# Board.net
KiCad netlist of a schematic drawn in EasyEDA Pro
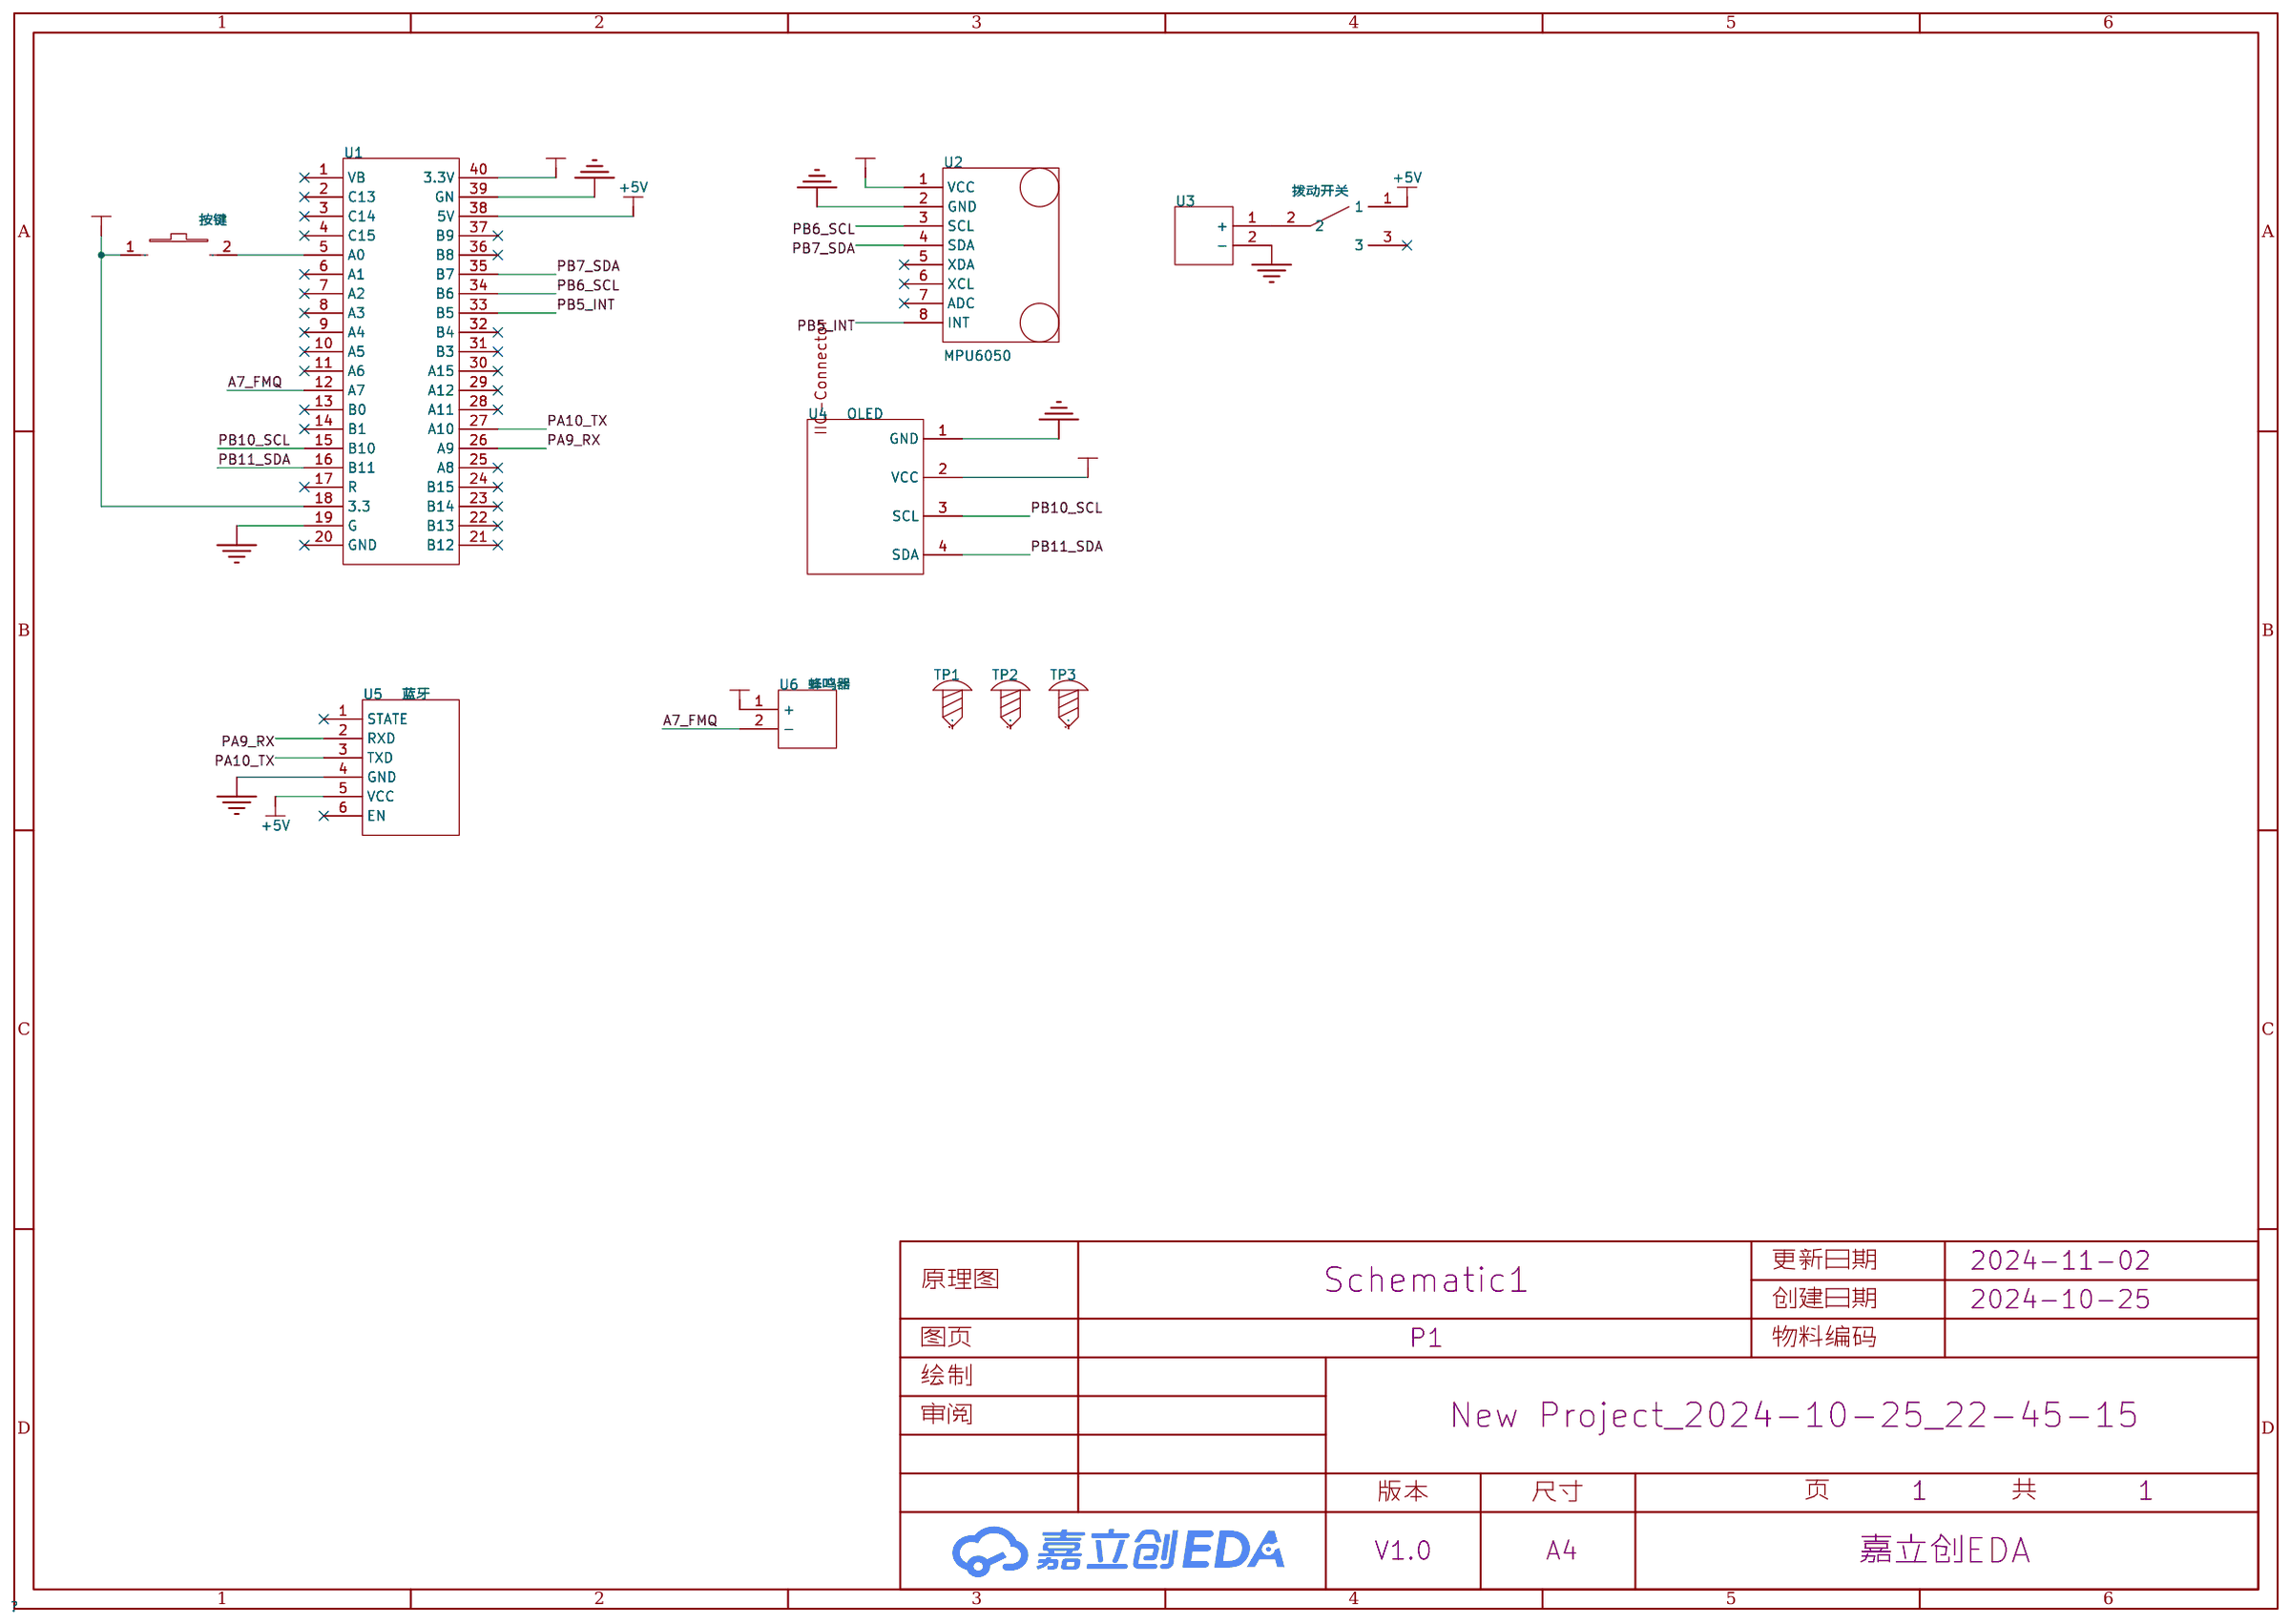
[diagram p0: schematic sheet]

(export (version "E")
  (design (tool "Eeschema 10.0.6"))
  (components
    (comp (ref "J1")
      (value "按键")
      (footprint "easyedapro:SW-SMD_L6.0-W3.6-LS8.0")
      (fields (field (name "Manufacturer Part") "轻触按键 3x6x2.5mm"))
      (libsource (lib "easyedapro") (part "按键"))
    )
    (comp (ref "J2")
      (value "拨动开关")
      (footprint "easyedapro:SS12D00G4 1*3")
      (libsource (lib "easyedapro") (part "拨动开关"))
    )
    (comp (ref "TP1") (value "~") (footprint "easyedapro:M3螺丝") (libsource (lib "easyedapro") (part "螺丝孔")))
    (comp (ref "TP2") (value "~") (footprint "easyedapro:M3螺丝") (libsource (lib "easyedapro") (part "螺丝孔")))
    (comp (ref "TP3") (value "~") (footprint "easyedapro:M3螺丝") (libsource (lib "easyedapro") (part "螺丝孔")))
    (comp (ref "U1")
      (value "STM32")
      (footprint "easyedapro:STM32F103C8T6最小系统板")
      (description "STM32F103C最小系统板")
      (libsource (lib "easyedapro") (part "STM32"))
    )
    (comp (ref "U2")
      (value "MPU6050")
      (footprint "easyedapro:MPU6050")
      (libsource (lib "easyedapro") (part "mpu6050"))
    )
    (comp (ref "U3") (value "~") (footprint "easyedapro:锂电池充电") (libsource (lib "easyedapro") (part "锂电池")))
    (comp (ref "U4")
      (value "OLED")
      (footprint "easyedapro:0.96OLED_4P")
      (fields (field (name "Manufacturer Part") "0.96OLED_4P_MODULE_JX"))
      (libsource (lib "easyedapro") (part "oled"))
    )
    (comp (ref "U5") (value "蓝牙") (footprint "easyedapro:蓝牙") (libsource (lib "easyedapro") (part "蓝牙")))
    (comp (ref "U6") (value "蜂鸣器") (footprint "easyedapro:蜂鸣器") (libsource (lib "easyedapro") (part "蜂鸣器")))
  )
  (nets
    (net (code "1") (name "+5V") (class "Default")
      (node (ref "J2") (pin "1") (pinfunction "1_1") (pintype "input"))
      (node (ref "U1") (pin "38") (pinfunction "5V_38") (pintype "bidirectional"))
      (node (ref "U5") (pin "5") (pinfunction "VCC_5") (pintype "input"))
    )
    (net (code "2") (name "/A7_FMQ") (class "Default")
      (node (ref "U1") (pin "12") (pinfunction "A7_12") (pintype "bidirectional"))
      (node (ref "U6") (pin "2") (pinfunction "-_2") (pintype "input"))
    )
    (net (code "3") (name "/PA9_RX") (class "Default")
      (node (ref "U1") (pin "26") (pinfunction "A9_26") (pintype "bidirectional"))
      (node (ref "U5") (pin "2") (pinfunction "RXD_2") (pintype "input"))
    )
    (net (code "4") (name "/PA10_TX") (class "Default")
      (node (ref "U1") (pin "27") (pinfunction "A10_27") (pintype "bidirectional"))
      (node (ref "U5") (pin "3") (pinfunction "TXD_3") (pintype "input"))
    )
    (net (code "5") (name "/PB5_INT") (class "Default")
      (node (ref "U1") (pin "33") (pinfunction "B5_33") (pintype "bidirectional"))
      (node (ref "U2") (pin "8") (pinfunction "INT_8") (pintype "input"))
    )
    (net (code "6") (name "/PB6_SCL") (class "Default")
      (node (ref "U1") (pin "34") (pinfunction "B6_34") (pintype "bidirectional"))
      (node (ref "U2") (pin "3") (pinfunction "SCL_3") (pintype "input"))
    )
    (net (code "7") (name "/PB7_SDA") (class "Default")
      (node (ref "U1") (pin "35") (pinfunction "B7_35") (pintype "bidirectional"))
      (node (ref "U2") (pin "4") (pinfunction "SDA_4") (pintype "input"))
    )
    (net (code "8") (name "/PB10_SCL") (class "Default")
      (node (ref "U1") (pin "15") (pinfunction "B10_15") (pintype "bidirectional"))
      (node (ref "U4") (pin "3") (pinfunction "SCL_3") (pintype "unspecified"))
    )
    (net (code "9") (name "/PB11_SDA") (class "Default")
      (node (ref "U1") (pin "16") (pinfunction "B11_16") (pintype "bidirectional"))
      (node (ref "U4") (pin "4") (pinfunction "SDA_4") (pintype "unspecified"))
    )
    (net (code "10") (name "3V3") (class "Default")
      (node (ref "J1") (pin "1") (pinfunction "1_1") (pintype "input"))
      (node (ref "U1") (pin "18") (pinfunction "3.3_18") (pintype "bidirectional"))
      (node (ref "U1") (pin "40") (pinfunction "3.3V_40") (pintype "bidirectional"))
      (node (ref "U2") (pin "1") (pinfunction "VCC_1") (pintype "input"))
      (node (ref "U4") (pin "2") (pinfunction "VCC_2") (pintype "unspecified"))
      (node (ref "U6") (pin "1") (pinfunction "+_1") (pintype "input"))
    )
    (net (code "11") (name "GND") (class "Default")
      (node (ref "U1") (pin "19") (pinfunction "G_19") (pintype "bidirectional"))
      (node (ref "U1") (pin "39") (pinfunction "GN_39") (pintype "bidirectional"))
      (node (ref "U2") (pin "2") (pinfunction "GND_2") (pintype "input"))
      (node (ref "U3") (pin "2") (pinfunction "-_2") (pintype "input"))
      (node (ref "U4") (pin "1") (pinfunction "GND_1") (pintype "unspecified"))
      (node (ref "U5") (pin "4") (pinfunction "GND_4") (pintype "input"))
    )
    (net (code "12") (name "Net-(U1-A0)") (class "Default")
      (node (ref "J1") (pin "2") (pinfunction "2_2") (pintype "input"))
      (node (ref "U1") (pin "5") (pinfunction "A0_5") (pintype "bidirectional"))
    )
    (net (code "13") (name "Net-(U3-+)") (class "Default")
      (node (ref "J2") (pin "2") (pinfunction "2_2") (pintype "input"))
      (node (ref "U3") (pin "1") (pinfunction "+_1") (pintype "input"))
    )
    (net (code "14") (name "unconnected-(J2-Pad3)") (class "Default")
      (node (ref "J2") (pin "3") (pinfunction "3_3") (pintype "input+no_connect"))
    )
    (net (code "15") (name "unconnected-(TP1-Pad1)") (class "Default")
      (node (ref "TP1") (pin "1") (pinfunction "1_1") (pintype "input"))
    )
    (net (code "16") (name "unconnected-(TP2-Pad1)") (class "Default")
      (node (ref "TP2") (pin "1") (pinfunction "1_1") (pintype "input"))
    )
    (net (code "17") (name "unconnected-(TP3-Pad1)") (class "Default")
      (node (ref "TP3") (pin "1") (pinfunction "1_1") (pintype "input"))
    )
    (net (code "18") (name "unconnected-(U1-A1-Pad6)") (class "Default")
      (node (ref "U1") (pin "6") (pinfunction "A1_6") (pintype "bidirectional+no_connect"))
    )
    (net (code "19") (name "unconnected-(U1-A2-Pad7)") (class "Default")
      (node (ref "U1") (pin "7") (pinfunction "A2_7") (pintype "bidirectional+no_connect"))
    )
    (net (code "20") (name "unconnected-(U1-A3-Pad8)") (class "Default")
      (node (ref "U1") (pin "8") (pinfunction "A3_8") (pintype "bidirectional+no_connect"))
    )
    (net (code "21") (name "unconnected-(U1-A4-Pad9)") (class "Default")
      (node (ref "U1") (pin "9") (pinfunction "A4_9") (pintype "bidirectional+no_connect"))
    )
    (net (code "22") (name "unconnected-(U1-A5-Pad10)") (class "Default")
      (node (ref "U1") (pin "10") (pinfunction "A5_10") (pintype "bidirectional+no_connect"))
    )
    (net (code "23") (name "unconnected-(U1-A6-Pad11)") (class "Default")
      (node (ref "U1") (pin "11") (pinfunction "A6_11") (pintype "bidirectional+no_connect"))
    )
    (net (code "24") (name "unconnected-(U1-A8-Pad25)") (class "Default")
      (node (ref "U1") (pin "25") (pinfunction "A8_25") (pintype "bidirectional+no_connect"))
    )
    (net (code "25") (name "unconnected-(U1-A11-Pad28)") (class "Default")
      (node (ref "U1") (pin "28") (pinfunction "A11_28") (pintype "bidirectional+no_connect"))
    )
    (net (code "26") (name "unconnected-(U1-A12-Pad29)") (class "Default")
      (node (ref "U1") (pin "29") (pinfunction "A12_29") (pintype "bidirectional+no_connect"))
    )
    (net (code "27") (name "unconnected-(U1-A15-Pad30)") (class "Default")
      (node (ref "U1") (pin "30") (pinfunction "A15_30") (pintype "bidirectional+no_connect"))
    )
    (net (code "28") (name "unconnected-(U1-B0-Pad13)") (class "Default")
      (node (ref "U1") (pin "13") (pinfunction "B0_13") (pintype "bidirectional+no_connect"))
    )
    (net (code "29") (name "unconnected-(U1-B1-Pad14)") (class "Default")
      (node (ref "U1") (pin "14") (pinfunction "B1_14") (pintype "bidirectional+no_connect"))
    )
    (net (code "30") (name "unconnected-(U1-B3-Pad31)") (class "Default")
      (node (ref "U1") (pin "31") (pinfunction "B3_31") (pintype "bidirectional+no_connect"))
    )
    (net (code "31") (name "unconnected-(U1-B4-Pad32)") (class "Default")
      (node (ref "U1") (pin "32") (pinfunction "B4_32") (pintype "bidirectional+no_connect"))
    )
    (net (code "32") (name "unconnected-(U1-B8-Pad36)") (class "Default")
      (node (ref "U1") (pin "36") (pinfunction "B8_36") (pintype "bidirectional+no_connect"))
    )
    (net (code "33") (name "unconnected-(U1-B9-Pad37)") (class "Default")
      (node (ref "U1") (pin "37") (pinfunction "B9_37") (pintype "bidirectional+no_connect"))
    )
    (net (code "34") (name "unconnected-(U1-B12-Pad21)") (class "Default")
      (node (ref "U1") (pin "21") (pinfunction "B12_21") (pintype "bidirectional+no_connect"))
    )
    (net (code "35") (name "unconnected-(U1-B13-Pad22)") (class "Default")
      (node (ref "U1") (pin "22") (pinfunction "B13_22") (pintype "bidirectional+no_connect"))
    )
    (net (code "36") (name "unconnected-(U1-B14-Pad23)") (class "Default")
      (node (ref "U1") (pin "23") (pinfunction "B14_23") (pintype "bidirectional+no_connect"))
    )
    (net (code "37") (name "unconnected-(U1-B15-Pad24)") (class "Default")
      (node (ref "U1") (pin "24") (pinfunction "B15_24") (pintype "bidirectional+no_connect"))
    )
    (net (code "38") (name "unconnected-(U1-C13-Pad2)") (class "Default")
      (node (ref "U1") (pin "2") (pinfunction "C13_2") (pintype "bidirectional+no_connect"))
    )
    (net (code "39") (name "unconnected-(U1-C14-Pad3)") (class "Default")
      (node (ref "U1") (pin "3") (pinfunction "C14_3") (pintype "bidirectional+no_connect"))
    )
    (net (code "40") (name "unconnected-(U1-C15-Pad4)") (class "Default")
      (node (ref "U1") (pin "4") (pinfunction "C15_4") (pintype "bidirectional+no_connect"))
    )
    (net (code "41") (name "unconnected-(U1-GND-Pad20)") (class "Default")
      (node (ref "U1") (pin "20") (pinfunction "GND_20") (pintype "bidirectional+no_connect"))
    )
    (net (code "42") (name "unconnected-(U1-R-Pad17)") (class "Default")
      (node (ref "U1") (pin "17") (pinfunction "R_17") (pintype "bidirectional+no_connect"))
    )
    (net (code "43") (name "unconnected-(U1-VB-Pad1)") (class "Default")
      (node (ref "U1") (pin "1") (pinfunction "VB_1") (pintype "bidirectional+no_connect"))
    )
    (net (code "44") (name "unconnected-(U2-ADC-Pad7)") (class "Default")
      (node (ref "U2") (pin "7") (pinfunction "ADC_7") (pintype "input+no_connect"))
    )
    (net (code "45") (name "unconnected-(U2-XCL-Pad6)") (class "Default")
      (node (ref "U2") (pin "6") (pinfunction "XCL_6") (pintype "input+no_connect"))
    )
    (net (code "46") (name "unconnected-(U2-XDA-Pad5)") (class "Default")
      (node (ref "U2") (pin "5") (pinfunction "XDA_5") (pintype "input+no_connect"))
    )
    (net (code "47") (name "unconnected-(U5-EN-Pad6)") (class "Default")
      (node (ref "U5") (pin "6") (pinfunction "EN_6") (pintype "input+no_connect"))
    )
    (net (code "48") (name "unconnected-(U5-STATE-Pad1)") (class "Default")
      (node (ref "U5") (pin "1") (pinfunction "STATE_1") (pintype "input+no_connect"))
    )
  )
)
